# Sheet4.net
KiCad netlist of a schematic drawn in Altium Designer
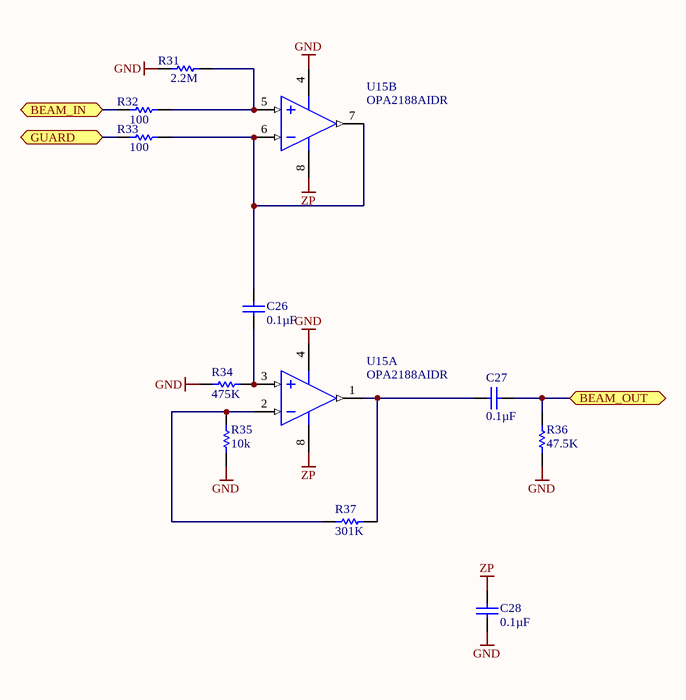
[diagram p0: Sheet4.SchDoc]

(export (version "E")
  (design (tool "Eeschema 10.0.6"))
  (components
    (comp (ref "C26")
      (value "CAP CER 0.1UF 25V X7R 0805")
      (footprint "CAPC0805(2012)145_N")
      (fields
        (field (name "MANUFACTURER") "Murata Electronics North America")
        (field (name "MANUFACTURER PART NUMBER") "GRM21BR71E104KA01L")
        (field (name "CAPACITANCE") "0.1µF")
        (field (name "TOLERANCE") "±10%")
      )
      (libsource (lib "Altium Content Vault") (part "CMP-1036-04795-1"))
    )
    (comp (ref "C27")
      (value "CAP CER 0.1UF 25V X7R 0805")
      (footprint "CAPC0805(2012)145_N")
      (fields
        (field (name "MANUFACTURER") "Murata Electronics North America")
        (field (name "MANUFACTURER PART NUMBER") "GRM21BR71E104KA01L")
        (field (name "CAPACITANCE") "0.1µF")
        (field (name "TOLERANCE") "±10%")
      )
      (libsource (lib "Altium Content Vault") (part "CMP-1036-04795-1"))
    )
    (comp (ref "C28")
      (value "CAP CER 0.1UF 25V X7R 0805")
      (footprint "CAPC0805(2012)145_N")
      (fields
        (field (name "MANUFACTURER") "Murata Electronics North America")
        (field (name "MANUFACTURER PART NUMBER") "GRM21BR71E104KA01L")
        (field (name "CAPACITANCE") "0.1µF")
        (field (name "TOLERANCE") "±10%")
      )
      (libsource (lib "Altium Content Vault") (part "CMP-1036-04795-1"))
    )
    (comp (ref "R31")
      (value "2.2M")
      (footprint "RESC0402(1005)_M")
      (description "RES SMD 10K OHM 1% 1/8W 0402")
      (fields
        (field (name "MANUFACTURER") "Vishay Dale")
        (field (name "MANUFACTURER PART NUMBER") "CRCW0402100KFKEDHP")
      )
      (libsource (lib "Altium Content Vault") (part "CMP-1011-00651-1"))
    )
    (comp (ref "R32")
      (value "100")
      (footprint "RESC0402(1005)_M")
      (description "RES SMD 10K OHM 1% 1/8W 0402")
      (fields
        (field (name "MANUFACTURER") "Vishay Dale")
        (field (name "MANUFACTURER PART NUMBER") "CRCW0402100KFKEDHP")
      )
      (libsource (lib "Altium Content Vault") (part "CMP-1011-00651-1"))
    )
    (comp (ref "R33")
      (value "100")
      (footprint "RESC0402(1005)_M")
      (description "RES SMD 10K OHM 1% 1/8W 0402")
      (fields
        (field (name "MANUFACTURER") "Vishay Dale")
        (field (name "MANUFACTURER PART NUMBER") "CRCW0402100KFKEDHP")
      )
      (libsource (lib "Altium Content Vault") (part "CMP-1011-00651-1"))
    )
    (comp (ref "R34")
      (value "475K")
      (footprint "RESC0402(1005)_M")
      (description "RES SMD 10K OHM 1% 1/8W 0402")
      (fields
        (field (name "MANUFACTURER") "Vishay Dale")
        (field (name "MANUFACTURER PART NUMBER") "CRCW0402100KFKEDHP")
      )
      (libsource (lib "Altium Content Vault") (part "CMP-1011-00651-1"))
    )
    (comp (ref "R35")
      (value "10k")
      (footprint "RESC0402(1005)_M")
      (description "RES SMD 10K OHM 1% 1/8W 0402")
      (fields
        (field (name "MANUFACTURER") "Vishay Dale")
        (field (name "MANUFACTURER PART NUMBER") "CRCW0402100KFKEDHP")
      )
      (libsource (lib "Altium Content Vault") (part "CMP-1011-00651-1"))
    )
    (comp (ref "R36")
      (value "47.5K")
      (footprint "RESC0402(1005)_M")
      (description "RES SMD 10K OHM 1% 1/8W 0402")
      (fields
        (field (name "MANUFACTURER") "Vishay Dale")
        (field (name "MANUFACTURER PART NUMBER") "CRCW0402100KFKEDHP")
      )
      (libsource (lib "Altium Content Vault") (part "CMP-1011-00651-1"))
    )
    (comp (ref "R37")
      (value "301K")
      (footprint "RESC0402(1005)_M")
      (description "RES SMD 10K OHM 1% 1/8W 0402")
      (fields
        (field (name "MANUFACTURER") "Vishay Dale")
        (field (name "MANUFACTURER PART NUMBER") "CRCW0402100KFKEDHP")
      )
      (libsource (lib "Altium Content Vault") (part "CMP-1011-00651-1"))
    )
    (comp (ref "U15")
      (value "OPA2188AIDR")
      (footprint "D0008A_L")
      (fields (field (name "MANUFACTURER") "Texas Instruments"))
      (libsource (lib "Altium Content Vault") (part "CMP-0272-00241-3"))
    )
  )
  (nets
    (net (code "1") (name "/BEAM_IN") (class "Default")
      (node (ref "R32") (pin "2") (pinfunction "2_2") (pintype "passive"))
    )
    (net (code "2") (name "/BEAM_OUT") (class "Default")
      (node (ref "C27") (pin "1") (pinfunction "1_1") (pintype "passive"))
      (node (ref "R36") (pin "1") (pinfunction "1_1") (pintype "passive"))
    )
    (net (code "3") (name "/GUARD") (class "Default")
      (node (ref "R33") (pin "2") (pinfunction "2_2") (pintype "passive"))
    )
    (net (code "4") (name "GND") (class "Default")
      (node (ref "C28") (pin "1") (pinfunction "1_1") (pintype "passive"))
      (node (ref "R31") (pin "2") (pinfunction "2_2") (pintype "passive"))
      (node (ref "R34") (pin "2") (pinfunction "2_2") (pintype "passive"))
      (node (ref "R35") (pin "2") (pinfunction "2_2") (pintype "passive"))
      (node (ref "R36") (pin "2") (pinfunction "2_2") (pintype "passive"))
      (node (ref "U15") (pin "4") (pinfunction "V-_4") (pintype "power_in"))
    )
    (net (code "5") (name "Net-(U15A-IN_A+)") (class "Default")
      (node (ref "C26") (pin "2") (pinfunction "2_2") (pintype "passive"))
      (node (ref "R34") (pin "1") (pinfunction "1_1") (pintype "passive"))
      (node (ref "U15") (pin "3") (pinfunction "IN_A+_3") (pintype "input"))
    )
    (net (code "6") (name "Net-(U15A-IN_A-)") (class "Default")
      (node (ref "R35") (pin "1") (pinfunction "1_1") (pintype "passive"))
      (node (ref "R37") (pin "2") (pinfunction "2_2") (pintype "passive"))
      (node (ref "U15") (pin "2") (pinfunction "IN_A-_2") (pintype "input"))
    )
    (net (code "7") (name "Net-(U15A-OUT_A)") (class "Default")
      (node (ref "C27") (pin "2") (pinfunction "2_2") (pintype "passive"))
      (node (ref "R37") (pin "1") (pinfunction "1_1") (pintype "passive"))
      (node (ref "U15") (pin "1") (pinfunction "OUT_A_1") (pintype "output"))
    )
    (net (code "8") (name "Net-(U15B-IN_B+)") (class "Default")
      (node (ref "R31") (pin "1") (pinfunction "1_1") (pintype "passive"))
      (node (ref "R32") (pin "1") (pinfunction "1_1") (pintype "passive"))
      (node (ref "U15") (pin "5") (pinfunction "IN_B+_5") (pintype "input"))
    )
    (net (code "9") (name "Net-(U15B-IN_B-)") (class "Default")
      (node (ref "C26") (pin "1") (pinfunction "1_1") (pintype "passive"))
      (node (ref "R33") (pin "1") (pinfunction "1_1") (pintype "passive"))
      (node (ref "U15") (pin "6") (pinfunction "IN_B-_6") (pintype "input"))
      (node (ref "U15") (pin "7") (pinfunction "OUT_B_7") (pintype "output"))
    )
    (net (code "10") (name "ZP") (class "Default")
      (node (ref "C28") (pin "2") (pinfunction "2_2") (pintype "passive"))
      (node (ref "U15") (pin "8") (pinfunction "V+_8") (pintype "power_in"))
    )
  )
)
